# PropGame_DevBoard_schema.net
KiCad netlist of a schematic drawn in EAGLE
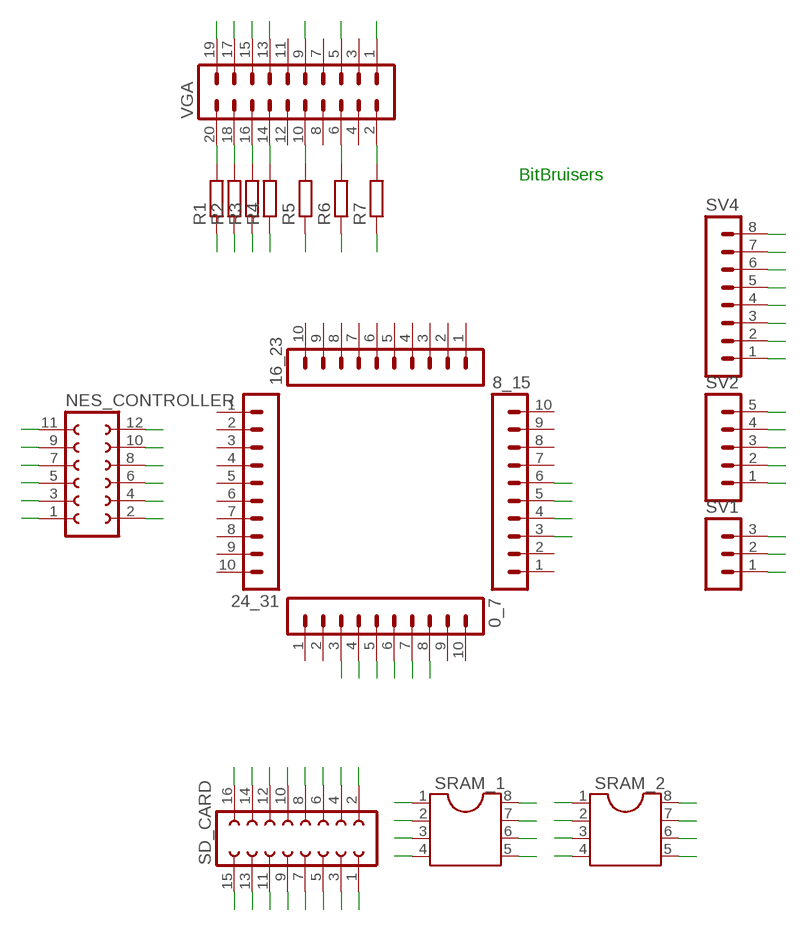
[diagram p0: schematic, sheet 1]

(export (version "E")
  (design (tool "Eeschema 10.0.6"))
  (components
    (comp (ref "0_7")
      (value "MA10-1")
      (footprint "eagle-import:MA10-1")
      (libsource (lib "eagle-import") (part "MA10-1"))
    )
    (comp (ref "8_15")
      (value "MA10-1")
      (footprint "eagle-import:MA10-1")
      (libsource (lib "eagle-import") (part "MA10-1"))
    )
    (comp (ref "16_23")
      (value "MA10-1")
      (footprint "eagle-import:MA10-1")
      (libsource (lib "eagle-import") (part "MA10-1"))
    )
    (comp (ref "24_31")
      (value "MA10-1")
      (footprint "eagle-import:MA10-1")
      (libsource (lib "eagle-import") (part "MA10-1"))
    )
    (comp (ref "NES_CONTROLLER")
      (value "FE06-2")
      (footprint "eagle-import:FE06-2")
      (libsource (lib "eagle-import") (part "FE06-2"))
    )
    (comp (ref "R1")
      (value "R-EU_0204/7")
      (footprint "eagle-import:0204_7")
      (libsource (lib "eagle-import") (part "R-EU_0204/7"))
    )
    (comp (ref "R2")
      (value "R-EU_0204/7")
      (footprint "eagle-import:0204_7")
      (libsource (lib "eagle-import") (part "R-EU_0204/7"))
    )
    (comp (ref "R3")
      (value "R-EU_0204/7")
      (footprint "eagle-import:0204_7")
      (libsource (lib "eagle-import") (part "R-EU_0204/7"))
    )
    (comp (ref "R4")
      (value "R-EU_0204/7")
      (footprint "eagle-import:0204_7")
      (libsource (lib "eagle-import") (part "R-EU_0204/7"))
    )
    (comp (ref "R5")
      (value "R-EU_0204/7")
      (footprint "eagle-import:0204_7")
      (libsource (lib "eagle-import") (part "R-EU_0204/7"))
    )
    (comp (ref "R6")
      (value "R-EU_0204/7")
      (footprint "eagle-import:0204_7")
      (libsource (lib "eagle-import") (part "R-EU_0204/7"))
    )
    (comp (ref "R7")
      (value "R-EU_0204/7")
      (footprint "eagle-import:0204_7")
      (libsource (lib "eagle-import") (part "R-EU_0204/7"))
    )
    (comp (ref "SD_CARD")
      (value "FE08-2")
      (footprint "eagle-import:FE08-2")
      (libsource (lib "eagle-import") (part "FE08-2"))
    )
    (comp (ref "SRAM_1")
      (value "DIL8")
      (footprint "eagle-import:DIL08")
      (libsource (lib "eagle-import") (part "DIL8"))
    )
    (comp (ref "SRAM_2")
      (value "DIL8")
      (footprint "eagle-import:DIL08")
      (libsource (lib "eagle-import") (part "DIL8"))
    )
    (comp (ref "SV1")
      (value "MA03-1")
      (footprint "eagle-import:MA03-1")
      (libsource (lib "eagle-import") (part "MA03-1"))
    )
    (comp (ref "SV2")
      (value "MA05-1")
      (footprint "eagle-import:MA05-1")
      (libsource (lib "eagle-import") (part "MA05-1"))
    )
    (comp (ref "SV4")
      (value "MA08-1")
      (footprint "eagle-import:MA08-1")
      (libsource (lib "eagle-import") (part "MA08-1"))
    )
    (comp (ref "VGA")
      (value "MA10-2")
      (footprint "eagle-import:MA10-2")
      (libsource (lib "eagle-import") (part "MA10-2"))
    )
  )
  (nets
    (net (code "1") (name "/3V3") (class "Default")
      (node (ref "SD_CARD") (pin "13") (pinfunction "13_13") (pintype "passive"))
      (node (ref "SD_CARD") (pin "14") (pinfunction "14_14") (pintype "passive"))
      (node (ref "SRAM_1") (pin "8") (pinfunction "8_8") (pintype "passive"))
      (node (ref "SRAM_2") (pin "8") (pinfunction "8_8") (pintype "passive"))
      (node (ref "SV1") (pin "1") (pinfunction "1_1") (pintype "passive"))
      (node (ref "SV1") (pin "2") (pinfunction "2_2") (pintype "passive"))
      (node (ref "SV1") (pin "3") (pinfunction "3_3") (pintype "passive"))
    )
    (net (code "2") (name "/5V") (class "Default")
      (node (ref "NES_CONTROLLER") (pin "3") (pinfunction "3_3") (pintype "passive"))
      (node (ref "NES_CONTROLLER") (pin "4") (pinfunction "4_4") (pintype "passive"))
      (node (ref "SD_CARD") (pin "11") (pinfunction "11_11") (pintype "passive"))
      (node (ref "SD_CARD") (pin "12") (pinfunction "12_12") (pintype "passive"))
      (node (ref "SV4") (pin "1") (pinfunction "1_1") (pintype "passive"))
      (node (ref "SV4") (pin "2") (pinfunction "2_2") (pintype "passive"))
      (node (ref "SV4") (pin "3") (pinfunction "3_3") (pintype "passive"))
    )
    (net (code "3") (name "/CLK") (class "Default")
      (node (ref "8_15") (pin "3") (pinfunction "3_3") (pintype "passive"))
      (node (ref "NES_CONTROLLER") (pin "11") (pinfunction "11_11") (pintype "passive"))
      (node (ref "NES_CONTROLLER") (pin "12") (pinfunction "12_12") (pintype "passive"))
    )
    (net (code "4") (name "/CS_1") (class "Default")
      (node (ref "0_7") (pin "6") (pinfunction "6_6") (pintype "passive"))
      (node (ref "SD_CARD") (pin "10") (pinfunction "10_10") (pintype "passive"))
      (node (ref "SD_CARD") (pin "9") (pinfunction "9_9") (pintype "passive"))
    )
    (net (code "5") (name "/CS_2") (class "Default")
      (node (ref "0_7") (pin "7") (pinfunction "7_7") (pintype "passive"))
      (node (ref "SRAM_1") (pin "1") (pinfunction "1_1") (pintype "passive"))
    )
    (net (code "6") (name "/CS_3") (class "Default")
      (node (ref "0_7") (pin "8") (pinfunction "8_8") (pintype "passive"))
      (node (ref "SRAM_2") (pin "1") (pinfunction "1_1") (pintype "passive"))
    )
    (net (code "7") (name "/DATA1") (class "Default")
      (node (ref "8_15") (pin "5") (pinfunction "5_5") (pintype "passive"))
      (node (ref "NES_CONTROLLER") (pin "7") (pinfunction "7_7") (pintype "passive"))
      (node (ref "NES_CONTROLLER") (pin "8") (pinfunction "8_8") (pintype "passive"))
    )
    (net (code "8") (name "/DATA2") (class "Default")
      (node (ref "8_15") (pin "6") (pinfunction "6_6") (pintype "passive"))
      (node (ref "NES_CONTROLLER") (pin "5") (pinfunction "5_5") (pintype "passive"))
      (node (ref "NES_CONTROLLER") (pin "6") (pinfunction "6_6") (pintype "passive"))
    )
    (net (code "9") (name "/GND") (class "Default")
      (node (ref "NES_CONTROLLER") (pin "1") (pinfunction "1_1") (pintype "passive"))
      (node (ref "NES_CONTROLLER") (pin "2") (pinfunction "2_2") (pintype "passive"))
      (node (ref "SD_CARD") (pin "1") (pinfunction "1_1") (pintype "passive"))
      (node (ref "SD_CARD") (pin "15") (pinfunction "15_15") (pintype "passive"))
      (node (ref "SD_CARD") (pin "16") (pinfunction "16_16") (pintype "passive"))
      (node (ref "SD_CARD") (pin "2") (pinfunction "2_2") (pintype "passive"))
      (node (ref "SRAM_1") (pin "4") (pinfunction "4_4") (pintype "passive"))
      (node (ref "SRAM_2") (pin "4") (pinfunction "4_4") (pintype "passive"))
      (node (ref "SV2") (pin "1") (pinfunction "1_1") (pintype "passive"))
      (node (ref "SV2") (pin "2") (pinfunction "2_2") (pintype "passive"))
      (node (ref "SV2") (pin "3") (pinfunction "3_3") (pintype "passive"))
      (node (ref "SV2") (pin "4") (pinfunction "4_4") (pintype "passive"))
      (node (ref "SV2") (pin "5") (pinfunction "5_5") (pintype "passive"))
      (node (ref "SV4") (pin "4") (pinfunction "4_4") (pintype "passive"))
      (node (ref "SV4") (pin "5") (pinfunction "5_5") (pintype "passive"))
      (node (ref "SV4") (pin "6") (pinfunction "6_6") (pintype "passive"))
      (node (ref "SV4") (pin "7") (pinfunction "7_7") (pintype "passive"))
      (node (ref "SV4") (pin "8") (pinfunction "8_8") (pintype "passive"))
    )
    (net (code "10") (name "/LATCH") (class "Default")
      (node (ref "8_15") (pin "4") (pinfunction "4_4") (pintype "passive"))
      (node (ref "NES_CONTROLLER") (pin "10") (pinfunction "10_10") (pintype "passive"))
      (node (ref "NES_CONTROLLER") (pin "9") (pinfunction "9_9") (pintype "passive"))
    )
    (net (code "11") (name "/MISO") (class "Default")
      (node (ref "0_7") (pin "5") (pinfunction "5_5") (pintype "passive"))
      (node (ref "SD_CARD") (pin "3") (pinfunction "3_3") (pintype "passive"))
      (node (ref "SD_CARD") (pin "4") (pinfunction "4_4") (pintype "passive"))
      (node (ref "SRAM_1") (pin "2") (pinfunction "2_2") (pintype "passive"))
      (node (ref "SRAM_2") (pin "2") (pinfunction "2_2") (pintype "passive"))
    )
    (net (code "12") (name "/MOSI") (class "Default")
      (node (ref "0_7") (pin "4") (pinfunction "4_4") (pintype "passive"))
      (node (ref "SD_CARD") (pin "7") (pinfunction "7_7") (pintype "passive"))
      (node (ref "SD_CARD") (pin "8") (pinfunction "8_8") (pintype "passive"))
      (node (ref "SRAM_1") (pin "5") (pinfunction "5_5") (pintype "passive"))
      (node (ref "SRAM_2") (pin "5") (pinfunction "5_5") (pintype "passive"))
    )
    (net (code "13") (name "/SCK") (class "Default")
      (node (ref "0_7") (pin "3") (pinfunction "3_3") (pintype "passive"))
      (node (ref "SD_CARD") (pin "5") (pinfunction "5_5") (pintype "passive"))
      (node (ref "SD_CARD") (pin "6") (pinfunction "6_6") (pintype "passive"))
      (node (ref "SRAM_1") (pin "6") (pinfunction "6_6") (pintype "passive"))
      (node (ref "SRAM_2") (pin "6") (pinfunction "6_6") (pintype "passive"))
    )
    (net (code "14") (name "/W_1") (class "Default")
      (node (ref "R1") (pin "1") (pinfunction "1_1") (pintype "passive"))
      (node (ref "VGA") (pin "19") (pinfunction "19_19") (pintype "passive"))
    )
    (net (code "15") (name "/W_2") (class "Default")
      (node (ref "R2") (pin "1") (pinfunction "1_1") (pintype "passive"))
      (node (ref "VGA") (pin "17") (pinfunction "17_17") (pintype "passive"))
    )
    (net (code "16") (name "/W_3") (class "Default")
      (node (ref "R3") (pin "1") (pinfunction "1_1") (pintype "passive"))
      (node (ref "VGA") (pin "15") (pinfunction "15_15") (pintype "passive"))
    )
    (net (code "17") (name "/W_4") (class "Default")
      (node (ref "R4") (pin "1") (pinfunction "1_1") (pintype "passive"))
      (node (ref "VGA") (pin "13") (pinfunction "13_13") (pintype "passive"))
    )
    (net (code "18") (name "/W_5") (class "Default")
      (node (ref "R5") (pin "1") (pinfunction "1_1") (pintype "passive"))
      (node (ref "VGA") (pin "9") (pinfunction "9_9") (pintype "passive"))
    )
    (net (code "19") (name "/W_6") (class "Default")
      (node (ref "R6") (pin "1") (pinfunction "1_1") (pintype "passive"))
      (node (ref "VGA") (pin "5") (pinfunction "5_5") (pintype "passive"))
    )
    (net (code "20") (name "/W_7") (class "Default")
      (node (ref "R7") (pin "1") (pinfunction "1_1") (pintype "passive"))
      (node (ref "VGA") (pin "1") (pinfunction "1_1") (pintype "passive"))
    )
    (net (code "21") (name "Net-(R1-Pad2)") (class "Default")
      (node (ref "R1") (pin "2") (pinfunction "2_2") (pintype "passive"))
      (node (ref "VGA") (pin "20") (pinfunction "20_20") (pintype "passive"))
    )
    (net (code "22") (name "Net-(R2-Pad2)") (class "Default")
      (node (ref "R2") (pin "2") (pinfunction "2_2") (pintype "passive"))
      (node (ref "VGA") (pin "18") (pinfunction "18_18") (pintype "passive"))
    )
    (net (code "23") (name "Net-(R3-Pad2)") (class "Default")
      (node (ref "R3") (pin "2") (pinfunction "2_2") (pintype "passive"))
      (node (ref "VGA") (pin "16") (pinfunction "16_16") (pintype "passive"))
    )
    (net (code "24") (name "Net-(R4-Pad2)") (class "Default")
      (node (ref "R4") (pin "2") (pinfunction "2_2") (pintype "passive"))
      (node (ref "VGA") (pin "14") (pinfunction "14_14") (pintype "passive"))
    )
    (net (code "25") (name "Net-(R5-Pad2)") (class "Default")
      (node (ref "R5") (pin "2") (pinfunction "2_2") (pintype "passive"))
      (node (ref "VGA") (pin "10") (pinfunction "10_10") (pintype "passive"))
    )
    (net (code "26") (name "Net-(R6-Pad2)") (class "Default")
      (node (ref "R6") (pin "2") (pinfunction "2_2") (pintype "passive"))
      (node (ref "VGA") (pin "6") (pinfunction "6_6") (pintype "passive"))
    )
    (net (code "27") (name "Net-(R7-Pad2)") (class "Default")
      (node (ref "R7") (pin "2") (pinfunction "2_2") (pintype "passive"))
      (node (ref "VGA") (pin "2") (pinfunction "2_2") (pintype "passive"))
    )
    (net (code "28") (name "unconnected-(0_7-Pad1)") (class "Default")
      (node (ref "0_7") (pin "1") (pinfunction "1_1") (pintype "passive"))
    )
    (net (code "29") (name "unconnected-(0_7-Pad2)") (class "Default")
      (node (ref "0_7") (pin "2") (pinfunction "2_2") (pintype "passive"))
    )
    (net (code "30") (name "unconnected-(0_7-Pad9)") (class "Default")
      (node (ref "0_7") (pin "9") (pinfunction "9_9") (pintype "passive"))
    )
    (net (code "31") (name "unconnected-(0_7-Pad10)") (class "Default")
      (node (ref "0_7") (pin "10") (pinfunction "10_10") (pintype "passive"))
    )
    (net (code "32") (name "unconnected-(8_15-Pad1)") (class "Default")
      (node (ref "8_15") (pin "1") (pinfunction "1_1") (pintype "passive"))
    )
    (net (code "33") (name "unconnected-(8_15-Pad2)") (class "Default")
      (node (ref "8_15") (pin "2") (pinfunction "2_2") (pintype "passive"))
    )
    (net (code "34") (name "unconnected-(8_15-Pad7)") (class "Default")
      (node (ref "8_15") (pin "7") (pinfunction "7_7") (pintype "passive"))
    )
    (net (code "35") (name "unconnected-(8_15-Pad8)") (class "Default")
      (node (ref "8_15") (pin "8") (pinfunction "8_8") (pintype "passive"))
    )
    (net (code "36") (name "unconnected-(8_15-Pad9)") (class "Default")
      (node (ref "8_15") (pin "9") (pinfunction "9_9") (pintype "passive"))
    )
    (net (code "37") (name "unconnected-(8_15-Pad10)") (class "Default")
      (node (ref "8_15") (pin "10") (pinfunction "10_10") (pintype "passive"))
    )
    (net (code "38") (name "unconnected-(16_23-Pad1)") (class "Default")
      (node (ref "16_23") (pin "1") (pinfunction "1_1") (pintype "passive"))
    )
    (net (code "39") (name "unconnected-(16_23-Pad2)") (class "Default")
      (node (ref "16_23") (pin "2") (pinfunction "2_2") (pintype "passive"))
    )
    (net (code "40") (name "unconnected-(16_23-Pad3)") (class "Default")
      (node (ref "16_23") (pin "3") (pinfunction "3_3") (pintype "passive"))
    )
    (net (code "41") (name "unconnected-(16_23-Pad4)") (class "Default")
      (node (ref "16_23") (pin "4") (pinfunction "4_4") (pintype "passive"))
    )
    (net (code "42") (name "unconnected-(16_23-Pad5)") (class "Default")
      (node (ref "16_23") (pin "5") (pinfunction "5_5") (pintype "passive"))
    )
    (net (code "43") (name "unconnected-(16_23-Pad6)") (class "Default")
      (node (ref "16_23") (pin "6") (pinfunction "6_6") (pintype "passive"))
    )
    (net (code "44") (name "unconnected-(16_23-Pad7)") (class "Default")
      (node (ref "16_23") (pin "7") (pinfunction "7_7") (pintype "passive"))
    )
    (net (code "45") (name "unconnected-(16_23-Pad8)") (class "Default")
      (node (ref "16_23") (pin "8") (pinfunction "8_8") (pintype "passive"))
    )
    (net (code "46") (name "unconnected-(16_23-Pad9)") (class "Default")
      (node (ref "16_23") (pin "9") (pinfunction "9_9") (pintype "passive"))
    )
    (net (code "47") (name "unconnected-(16_23-Pad10)") (class "Default")
      (node (ref "16_23") (pin "10") (pinfunction "10_10") (pintype "passive"))
    )
    (net (code "48") (name "unconnected-(24_31-Pad1)") (class "Default")
      (node (ref "24_31") (pin "1") (pinfunction "1_1") (pintype "passive"))
    )
    (net (code "49") (name "unconnected-(24_31-Pad2)") (class "Default")
      (node (ref "24_31") (pin "2") (pinfunction "2_2") (pintype "passive"))
    )
    (net (code "50") (name "unconnected-(24_31-Pad3)") (class "Default")
      (node (ref "24_31") (pin "3") (pinfunction "3_3") (pintype "passive"))
    )
    (net (code "51") (name "unconnected-(24_31-Pad4)") (class "Default")
      (node (ref "24_31") (pin "4") (pinfunction "4_4") (pintype "passive"))
    )
    (net (code "52") (name "unconnected-(24_31-Pad5)") (class "Default")
      (node (ref "24_31") (pin "5") (pinfunction "5_5") (pintype "passive"))
    )
    (net (code "53") (name "unconnected-(24_31-Pad6)") (class "Default")
      (node (ref "24_31") (pin "6") (pinfunction "6_6") (pintype "passive"))
    )
    (net (code "54") (name "unconnected-(24_31-Pad7)") (class "Default")
      (node (ref "24_31") (pin "7") (pinfunction "7_7") (pintype "passive"))
    )
    (net (code "55") (name "unconnected-(24_31-Pad8)") (class "Default")
      (node (ref "24_31") (pin "8") (pinfunction "8_8") (pintype "passive"))
    )
    (net (code "56") (name "unconnected-(24_31-Pad9)") (class "Default")
      (node (ref "24_31") (pin "9") (pinfunction "9_9") (pintype "passive"))
    )
    (net (code "57") (name "unconnected-(24_31-Pad10)") (class "Default")
      (node (ref "24_31") (pin "10") (pinfunction "10_10") (pintype "passive"))
    )
    (net (code "58") (name "unconnected-(SRAM_1-Pad3)") (class "Default")
      (node (ref "SRAM_1") (pin "3") (pinfunction "3_3") (pintype "passive"))
    )
    (net (code "59") (name "unconnected-(SRAM_1-Pad7)") (class "Default")
      (node (ref "SRAM_1") (pin "7") (pinfunction "7_7") (pintype "passive"))
    )
    (net (code "60") (name "unconnected-(SRAM_2-Pad3)") (class "Default")
      (node (ref "SRAM_2") (pin "3") (pinfunction "3_3") (pintype "passive"))
    )
    (net (code "61") (name "unconnected-(SRAM_2-Pad7)") (class "Default")
      (node (ref "SRAM_2") (pin "7") (pinfunction "7_7") (pintype "passive"))
    )
    (net (code "62") (name "unconnected-(VGA-Pad3)") (class "Default")
      (node (ref "VGA") (pin "3") (pinfunction "3_3") (pintype "passive"))
    )
    (net (code "63") (name "unconnected-(VGA-Pad4)") (class "Default")
      (node (ref "VGA") (pin "4") (pinfunction "4_4") (pintype "passive"))
    )
    (net (code "64") (name "unconnected-(VGA-Pad7)") (class "Default")
      (node (ref "VGA") (pin "7") (pinfunction "7_7") (pintype "passive"))
    )
    (net (code "65") (name "unconnected-(VGA-Pad8)") (class "Default")
      (node (ref "VGA") (pin "8") (pinfunction "8_8") (pintype "passive"))
    )
    (net (code "66") (name "unconnected-(VGA-Pad11)") (class "Default")
      (node (ref "VGA") (pin "11") (pinfunction "11_11") (pintype "passive"))
    )
    (net (code "67") (name "unconnected-(VGA-Pad12)") (class "Default")
      (node (ref "VGA") (pin "12") (pinfunction "12_12") (pintype "passive"))
    )
  )
)
